# Power.net
KiCad netlist of a schematic drawn in Altium Designer
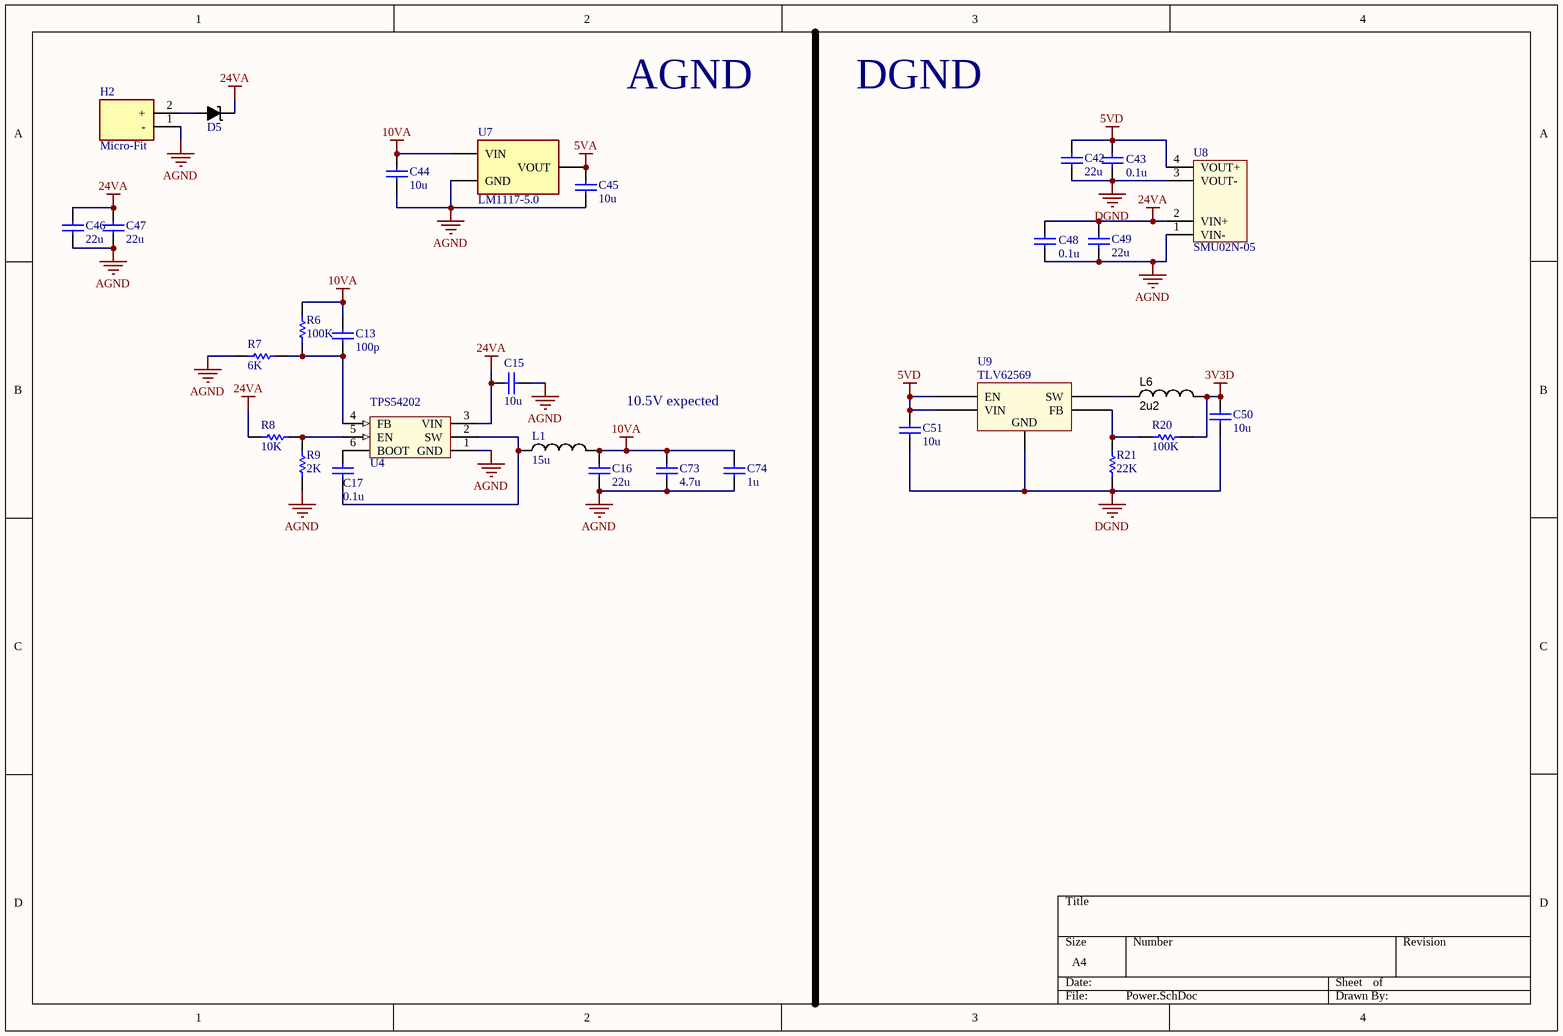
[diagram p0: Power.SchDoc]

(export (version "E")
  (design (tool "Eeschema 10.0.6"))
  (components
    (comp (ref "C13")
      (value "100p")
      (footprint "CAPC1608X90N")
      (description "Capacitor")
      (fields (field (name "Comment") "Cap") (field (name "PUBLISHER") "Altium Limited"))
      (libsource (lib "IOBoard_Low") (part "Cap"))
    )
    (comp (ref "C15")
      (value "10u")
      (footprint "CAPC2012X135N")
      (description "Capacitor")
      (fields (field (name "Comment") "Cap") (field (name "PUBLISHER") "Altium Limited"))
      (libsource (lib "IOBoard_Low") (part "Cap"))
    )
    (comp (ref "C16")
      (value "22u")
      (footprint "CAPC2012X135N")
      (description "Capacitor")
      (fields (field (name "Comment") "Cap") (field (name "PUBLISHER") "Altium Limited"))
      (libsource (lib "IOBoard_Low") (part "Cap"))
    )
    (comp (ref "C17")
      (value "0.1u")
      (footprint "CAPC1608X90N")
      (description "Capacitor")
      (fields (field (name "Comment") "Cap") (field (name "PUBLISHER") "Altium Limited"))
      (libsource (lib "IOBoard_Low") (part "Cap"))
    )
    (comp (ref "C42")
      (value "22u")
      (footprint "CAPC2012X135N")
      (description "Capacitor")
      (fields (field (name "Comment") "Cap") (field (name "PUBLISHER") "Altium Limited"))
      (libsource (lib "IOBoard_Low") (part "Cap"))
    )
    (comp (ref "C43")
      (value "0.1u")
      (footprint "CAPC1608X90N")
      (description "Capacitor")
      (fields (field (name "Comment") "Cap") (field (name "PUBLISHER") "Altium Limited"))
      (libsource (lib "IOBoard_Low") (part "Cap"))
    )
    (comp (ref "C44")
      (value "10u")
      (footprint "CAPC2012X135N")
      (description "Capacitor")
      (fields (field (name "Comment") "Cap") (field (name "PUBLISHER") "Altium Limited"))
      (libsource (lib "IOBoard_Low") (part "Cap"))
    )
    (comp (ref "C45")
      (value "10u")
      (footprint "CAPC2012X135N")
      (description "Capacitor")
      (fields (field (name "Comment") "Cap") (field (name "PUBLISHER") "Altium Limited"))
      (libsource (lib "IOBoard_Low") (part "Cap"))
    )
    (comp (ref "C46")
      (value "22u")
      (footprint "CAPC2012X135N")
      (description "Capacitor")
      (fields (field (name "Comment") "Cap") (field (name "PUBLISHER") "Altium Limited"))
      (libsource (lib "IOBoard_Low") (part "Cap"))
    )
    (comp (ref "C47")
      (value "22u")
      (footprint "CAPC2012X135N")
      (description "Capacitor")
      (fields (field (name "Comment") "Cap") (field (name "PUBLISHER") "Altium Limited"))
      (libsource (lib "IOBoard_Low") (part "Cap"))
    )
    (comp (ref "C48")
      (value "0.1u")
      (footprint "CAPC1608X90N")
      (description "Capacitor")
      (fields (field (name "Comment") "Cap") (field (name "PUBLISHER") "Altium Limited"))
      (libsource (lib "IOBoard_Low") (part "Cap"))
    )
    (comp (ref "C49")
      (value "22u")
      (footprint "CAPC2012X135N")
      (description "Capacitor")
      (fields (field (name "Comment") "Cap") (field (name "PUBLISHER") "Altium Limited"))
      (libsource (lib "IOBoard_Low") (part "Cap"))
    )
    (comp (ref "C50")
      (value "10u")
      (footprint "CAPC2012X135N")
      (description "Capacitor")
      (fields (field (name "Comment") "Cap") (field (name "PUBLISHER") "Altium Limited"))
      (libsource (lib "IOBoard_Low") (part "Cap"))
    )
    (comp (ref "C51")
      (value "10u")
      (footprint "CAPC2012X135N")
      (description "Capacitor")
      (fields (field (name "Comment") "Cap") (field (name "PUBLISHER") "Altium Limited"))
      (libsource (lib "IOBoard_Low") (part "Cap"))
    )
    (comp (ref "C73")
      (value "4.7u")
      (footprint "CAPC1608X90N")
      (description "Capacitor")
      (fields (field (name "Comment") "Cap") (field (name "PUBLISHER") "Altium Limited"))
      (libsource (lib "IOBoard_Low") (part "Cap"))
    )
    (comp (ref "C74")
      (value "1u")
      (footprint "CAPC1608X90N")
      (description "Capacitor")
      (fields (field (name "Comment") "Cap") (field (name "PUBLISHER") "Altium Limited"))
      (libsource (lib "IOBoard_Low") (part "Cap"))
    )
    (comp (ref "D5")
      (value "SS24")
      (footprint "DO-214AA")
      (description "2.0A SURFACE MOUNT SCHOTTKY BARRIER RECTIFIER")
      (fields (field (name "VOLTAGE") "40V"))
      (libsource (lib "IOBoard_Low") (part "SS24"))
    )
    (comp (ref "H2")
      (value "Micro-Fit")
      (footprint "430450212")
      (description "Micro fit series from MOLEX. 2P. 8.6A")
      (libsource (lib "IOBoard_Low") (part "Molex_430450212"))
    )
    (comp (ref "L1")
      (value "15u")
      (footprint "INDC_5.5x5.3x3")
      (description "15uH inductor with 2A saturation current. Dimension is 5.5 * 5.2 * 3 mm^3")
      (fields (field (name "Comment") "15uH inductor"))
      (libsource (lib "IOBoard_Low") (part "INDC_MPX1D0530L150"))
    )
    (comp (ref "L6")
      (value "2u2")
      (footprint "INDM3225X240N")
      (description "IHLP SMD 4040")
      (fields (field (name "Comment") "inductor"))
      (libsource (lib "IOBoard_Low") (part "INDC"))
    )
    (comp (ref "R6")
      (value "100K")
      (footprint "RESC1608X55N")
      (description "Resistor")
      (fields (field (name "Comment") "Res1") (field (name "PUBLISHER") "Altium Limited"))
      (libsource (lib "IOBoard_Low") (part "Res1"))
    )
    (comp (ref "R7")
      (value "6K")
      (footprint "RESC1608X55N")
      (description "Resistor")
      (fields (field (name "Comment") "Res1") (field (name "PUBLISHER") "Altium Limited"))
      (libsource (lib "IOBoard_Low") (part "Res1"))
    )
    (comp (ref "R8")
      (value "10K")
      (footprint "RESC1608X55N")
      (description "Resistor")
      (fields (field (name "Comment") "Res1") (field (name "PUBLISHER") "Altium Limited"))
      (libsource (lib "IOBoard_Low") (part "Res1"))
    )
    (comp (ref "R9")
      (value "2K")
      (footprint "RESC1608X55N")
      (description "Resistor")
      (fields (field (name "Comment") "Res1") (field (name "PUBLISHER") "Altium Limited"))
      (libsource (lib "IOBoard_Low") (part "Res1"))
    )
    (comp (ref "R20")
      (value "100K")
      (footprint "RESC2012X70N")
      (description "Resistor")
      (fields (field (name "Comment") "Res1") (field (name "PUBLISHER") "Altium Limited"))
      (libsource (lib "IOBoard_Low") (part "Res1"))
    )
    (comp (ref "R21")
      (value "22K")
      (footprint "RESC2012X70N")
      (description "Resistor")
      (fields (field (name "Comment") "Res1") (field (name "PUBLISHER") "Altium Limited"))
      (libsource (lib "IOBoard_Low") (part "Res1"))
    )
    (comp (ref "U4")
      (value "TPS54202")
      (footprint "SOT23-6")
      (description "4.5-28V input 2A output step down, EMI Friendly Synchronous Step Down Converter")
      (libsource (lib "IOBoard_Low") (part "TPS54202"))
    )
    (comp (ref "U7")
      (value "LM1117-5.0")
      (footprint "SOT223")
      (description "1117 LDO with fixed 5V output, 800mA current")
      (libsource (lib "IOBoard_Low") (part "LM1117-5.0"))
    )
    (comp (ref "U8")
      (value "SMU02N-05")
      (footprint "SMU02N")
      (description "isolated 24V to 5V")
      (libsource (lib "IOBoard_Low") (part "SMU02N-05"))
    )
    (comp (ref "U9")
      (value "TLV62569")
      (footprint "SOT23-5")
      (description "2-A High Efficiency Synchronous Buck Converter in SOT Package")
      (fields (field (name "MANUFACTURER") "TI"))
      (libsource (lib "IOBoard") (part "TLV62569"))
    )
  )
  (nets
    (net (code "1") (name "3V3D") (class "Default")
      (node (ref "C50") (pin "2") (pinfunction "2_2") (pintype "passive"))
      (node (ref "L6") (pin "2") (pinfunction "2_2") (pintype "passive"))
      (node (ref "R20") (pin "1") (pinfunction "1_1") (pintype "passive"))
    )
    (net (code "2") (name "5VA") (class "Default")
      (node (ref "C45") (pin "2") (pinfunction "2_2") (pintype "passive"))
      (node (ref "U7") (pin "2") (pinfunction "VOUT_2") (pintype "passive"))
      (node (ref "U7") (pin "4") (pinfunction "VOUT_4") (pintype "passive"))
    )
    (net (code "3") (name "5VD") (class "Default")
      (node (ref "C42") (pin "2") (pinfunction "2_2") (pintype "passive"))
      (node (ref "C43") (pin "2") (pinfunction "2_2") (pintype "passive"))
      (node (ref "C51") (pin "2") (pinfunction "2_2") (pintype "passive"))
      (node (ref "U8") (pin "4") (pinfunction "VOUT+_4") (pintype "power_in"))
      (node (ref "U9") (pin "1") (pinfunction "EN_1") (pintype "passive"))
      (node (ref "U9") (pin "4") (pinfunction "VIN_4") (pintype "passive"))
    )
    (net (code "4") (name "10VA") (class "Default")
      (node (ref "C13") (pin "2") (pinfunction "2_2") (pintype "passive"))
      (node (ref "C16") (pin "2") (pinfunction "2_2") (pintype "passive"))
      (node (ref "C44") (pin "2") (pinfunction "2_2") (pintype "passive"))
      (node (ref "C73") (pin "2") (pinfunction "2_2") (pintype "passive"))
      (node (ref "C74") (pin "2") (pinfunction "2_2") (pintype "passive"))
      (node (ref "L1") (pin "2") (pinfunction "2_2") (pintype "passive"))
      (node (ref "R6") (pin "2") (pinfunction "2_2") (pintype "passive"))
      (node (ref "U7") (pin "3") (pinfunction "VIN_3") (pintype "passive"))
    )
    (net (code "5") (name "24VA") (class "Default")
      (node (ref "C15") (pin "1") (pinfunction "1_1") (pintype "passive"))
      (node (ref "C46") (pin "2") (pinfunction "2_2") (pintype "passive"))
      (node (ref "C47") (pin "2") (pinfunction "2_2") (pintype "passive"))
      (node (ref "C48") (pin "2") (pinfunction "2_2") (pintype "passive"))
      (node (ref "C49") (pin "2") (pinfunction "2_2") (pintype "passive"))
      (node (ref "D5") (pin "K") (pinfunction "Cathode_K") (pintype "passive"))
      (node (ref "R8") (pin "1") (pinfunction "1_1") (pintype "passive"))
      (node (ref "U4") (pin "3") (pinfunction "VIN_3") (pintype "power_in"))
      (node (ref "U8") (pin "2") (pinfunction "VIN+_2") (pintype "power_in"))
    )
    (net (code "6") (name "AGND") (class "Default")
      (node (ref "C15") (pin "2") (pinfunction "2_2") (pintype "passive"))
      (node (ref "C16") (pin "1") (pinfunction "1_1") (pintype "passive"))
      (node (ref "C44") (pin "1") (pinfunction "1_1") (pintype "passive"))
      (node (ref "C45") (pin "1") (pinfunction "1_1") (pintype "passive"))
      (node (ref "C46") (pin "1") (pinfunction "1_1") (pintype "passive"))
      (node (ref "C47") (pin "1") (pinfunction "1_1") (pintype "passive"))
      (node (ref "C48") (pin "1") (pinfunction "1_1") (pintype "passive"))
      (node (ref "C49") (pin "1") (pinfunction "1_1") (pintype "passive"))
      (node (ref "C73") (pin "1") (pinfunction "1_1") (pintype "passive"))
      (node (ref "C74") (pin "1") (pinfunction "1_1") (pintype "passive"))
      (node (ref "H2") (pin "1") (pinfunction "-_1") (pintype "passive"))
      (node (ref "R7") (pin "2") (pinfunction "2_2") (pintype "passive"))
      (node (ref "R9") (pin "1") (pinfunction "1_1") (pintype "passive"))
      (node (ref "U4") (pin "1") (pinfunction "GND_1") (pintype "power_in"))
      (node (ref "U7") (pin "1") (pinfunction "GND_1") (pintype "passive"))
      (node (ref "U8") (pin "1") (pinfunction "VIN-_1") (pintype "power_in"))
    )
    (net (code "7") (name "DGND") (class "Default")
      (node (ref "C42") (pin "1") (pinfunction "1_1") (pintype "passive"))
      (node (ref "C43") (pin "1") (pinfunction "1_1") (pintype "passive"))
      (node (ref "C50") (pin "1") (pinfunction "1_1") (pintype "passive"))
      (node (ref "C51") (pin "1") (pinfunction "1_1") (pintype "passive"))
      (node (ref "R21") (pin "2") (pinfunction "2_2") (pintype "passive"))
      (node (ref "U8") (pin "3") (pinfunction "VOUT-_3") (pintype "power_in"))
      (node (ref "U9") (pin "2") (pinfunction "GND_2") (pintype "passive"))
    )
    (net (code "8") (name "Net-(D5-Anode)") (class "Default")
      (node (ref "D5") (pin "A") (pinfunction "Anode_A") (pintype "passive"))
      (node (ref "H2") (pin "2") (pinfunction "+_2") (pintype "passive"))
    )
    (net (code "9") (name "Net-(U4-BOOT)") (class "Default")
      (node (ref "C17") (pin "2") (pinfunction "2_2") (pintype "passive"))
      (node (ref "U4") (pin "6") (pinfunction "BOOT_6") (pintype "passive"))
    )
    (net (code "10") (name "Net-(U4-EN)") (class "Default")
      (node (ref "R8") (pin "2") (pinfunction "2_2") (pintype "passive"))
      (node (ref "R9") (pin "2") (pinfunction "2_2") (pintype "passive"))
      (node (ref "U4") (pin "5") (pinfunction "EN_5") (pintype "input"))
    )
    (net (code "11") (name "Net-(U4-FB)") (class "Default")
      (node (ref "C13") (pin "1") (pinfunction "1_1") (pintype "passive"))
      (node (ref "R6") (pin "1") (pinfunction "1_1") (pintype "passive"))
      (node (ref "R7") (pin "1") (pinfunction "1_1") (pintype "passive"))
      (node (ref "U4") (pin "4") (pinfunction "FB_4") (pintype "input"))
    )
    (net (code "12") (name "Net-(U4-SW)") (class "Default")
      (node (ref "C17") (pin "1") (pinfunction "1_1") (pintype "passive"))
      (node (ref "L1") (pin "1") (pinfunction "1_1") (pintype "passive"))
      (node (ref "U4") (pin "2") (pinfunction "SW_2") (pintype "power_in"))
    )
    (net (code "13") (name "Net-(U9-FB)") (class "Default")
      (node (ref "R20") (pin "2") (pinfunction "2_2") (pintype "passive"))
      (node (ref "R21") (pin "1") (pinfunction "1_1") (pintype "passive"))
      (node (ref "U9") (pin "5") (pinfunction "FB_5") (pintype "passive"))
    )
    (net (code "14") (name "Net-(U9-SW)") (class "Default")
      (node (ref "L6") (pin "1") (pinfunction "1_1") (pintype "passive"))
      (node (ref "U9") (pin "3") (pinfunction "SW_3") (pintype "passive"))
    )
  )
)
